# Receiver.net
KiCad netlist of a schematic drawn in Altium Designer
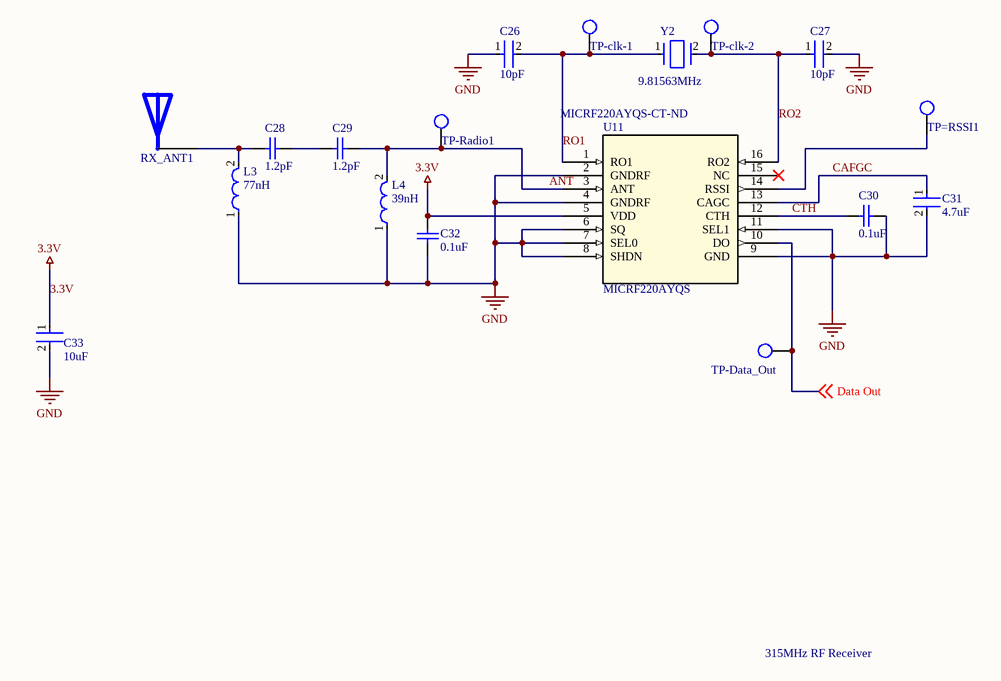
[diagram p0: Receiver.SchDoc]

(export (version "E")
  (design (tool "Eeschema 10.0.6"))
  (components
    (comp (ref "C26")
      (value "10pF")
      (footprint "FP-C0603C-CF-MFG")
      (description "CAP CER 10PF 50V NP0 0603")
      (fields
        (field (name "MANUFACTURER") "KEMET")
        (field (name "MANUFACTURER PART NUMBER") "C0603C100D5GACTU")
      )
      (libsource (lib "Altium Content Vault") (part "b4654b650e69147ec39a6b967a45e02"))
    )
    (comp (ref "C27")
      (value "10pF")
      (footprint "FP-C0603C-CF-MFG")
      (description "CAP CER 10PF 50V NP0 0603")
      (fields
        (field (name "MANUFACTURER") "KEMET")
        (field (name "MANUFACTURER PART NUMBER") "C0603C100D5GACTU")
      )
      (libsource (lib "Altium Content Vault") (part "b4654b650e69147ec39a6b967a45e02"))
    )
    (comp (ref "C28")
      (value "1.2pF")
      (footprint "CAPC1005X55X25LL05T10")
      (fields (field (name "PART NUMBER") "GRM1555C1H1R2WA01D") (field (name "MANUFACTURER") "Murata"))
      (libsource (lib "Altium Content Vault") (part "CAP"))
    )
    (comp (ref "C29")
      (value "1.2pF")
      (footprint "CAPC1005X55X25LL05T10")
      (fields (field (name "PART NUMBER") "GRM1555C1H1R2WA01D") (field (name "MANUFACTURER") "Murata"))
      (libsource (lib "Altium Content Vault") (part "CAP"))
    )
    (comp (ref "C30")
      (value "0.1uF")
      (footprint "CAPC1005X56X25LL10T15")
      (fields
        (field (name "MANUFACTURER") "AVX Interconnect / Elco")
        (field (name "PART NUMBER") "04026D104KAT2A")
      )
      (libsource (lib "Altium Content Vault") (part "CAP"))
    )
    (comp (ref "C31")
      (value "4.7uF")
      (footprint "FP-C1005-050-0_15-IPC_C")
      (description "CAP CER 4.7UF 6.3V X5R 0402")
      (fields (field (name "VOLTAGE") "6.3V") (field (name "TOLERANCE") "20%"))
      (libsource (lib "Altium Content Vault") (part "02cd4be3c70576c341d710602a673aa"))
    )
    (comp (ref "C32")
      (value "0.1uF")
      (footprint "CAPC1005X56X25LL10T15")
      (fields
        (field (name "MANUFACTURER") "AVX Interconnect / Elco")
        (field (name "PART NUMBER") "04026D104KAT2A")
      )
      (libsource (lib "Altium Content Vault") (part "CAP"))
    )
    (comp (ref "C33")
      (value "10uF")
      (footprint "FP-C0805C-DG-MFG")
      (description "CAP CER 10UF 10V X5R 0805")
      (fields (field (name "TOLERANCE") "10%") (field (name "MANUFACTURER PART NUMBER") "C0805C106K8PACTU"))
      (libsource (lib "Altium Content Vault") (part "11868f565c42a9108669ba33697ecf6"))
    )
    (comp (ref "L3")
      (value "77nH")
      (footprint "FP-LQW15CN_10-MFG")
      (description "Wire Wound Ferrite RF Inductor For Automotive 77nH ±5% 1100mA 0.09Ω 0402 (1005)")
      (fields (field (name "TOLERANCE") "5%"))
      (libsource (lib "Altium Content Vault") (part "725321dda6339637d4d059423bc1c3c"))
    )
    (comp (ref "L4")
      (value "39nH")
      (footprint "FP-LQW15AN_80-MFG")
      (description "Wire Wound RF Inductor 39nH ±5% 530mA 0.456Ω 0402 (1005)")
      (fields (field (name "TOLERANCE") "5%"))
      (libsource (lib "Altium Content Vault") (part "725321dda6339637d4d059423bc1c3c"))
    )
    (comp (ref "RX_ANT1")
      (value "RX Antenna")
      (footprint "RX_Antenna")
      (libsource (lib "team6") (part "RX Antenna"))
    )
    (comp (ref "TP-clk-1")
      (value "TP_1206")
      (footprint "TP-SMC-1206")
      (description "Test Point SMD 1206")
      (fields
        (field (name "MANUFACTURER") "TE Connectivity (Tyco Electronics)")
        (field (name "MANUFACTURER PART NUMBER") "1625854-1")
      )
      (libsource (lib "Mechanical") (part "TP_1206"))
    )
    (comp (ref "TP-clk-2")
      (value "TP_1206")
      (footprint "TP-SMC-1206")
      (description "Test Point SMD 1206")
      (fields
        (field (name "MANUFACTURER") "TE Connectivity (Tyco Electronics)")
        (field (name "MANUFACTURER PART NUMBER") "1625854-1")
      )
      (libsource (lib "Mechanical") (part "TP_1206"))
    )
    (comp (ref "TP-Data_Out")
      (value "TP_1206")
      (footprint "TP-SMC-1206")
      (description "Test Point SMD 1206")
      (fields
        (field (name "MANUFACTURER") "TE Connectivity (Tyco Electronics)")
        (field (name "MANUFACTURER PART NUMBER") "1625854-1")
      )
      (libsource (lib "Mechanical") (part "TP_1206"))
    )
    (comp (ref "TP-Radio1")
      (value "TP_1206")
      (footprint "TP-SMC-1206")
      (description "Test Point SMD 1206")
      (fields
        (field (name "MANUFACTURER") "TE Connectivity (Tyco Electronics)")
        (field (name "MANUFACTURER PART NUMBER") "1625854-1")
      )
      (libsource (lib "Mechanical") (part "TP_1206"))
    )
    (comp (ref "TP=RSSI1")
      (value "TP_1206")
      (footprint "TP-SMC-1206")
      (description "Test Point SMD 1206")
      (fields
        (field (name "MANUFACTURER") "TE Connectivity (Tyco Electronics)")
        (field (name "MANUFACTURER PART NUMBER") "1625854-1")
      )
      (libsource (lib "Mechanical") (part "TP_1206"))
    )
    (comp (ref "U11")
      (value "MICRF220AYQS")
      (footprint "SOP63P600X175-16N")
      (description "No Description Available")
      (fields
        (field (name "SUPPLIER PART NUMBER 1") "MICRF220AYQS-CT-ND")
        (field (name "COPYRIGHT") "Copyright (C) 2022 Ultra Librarian. All rights reserved.")
      )
      (libsource (lib "MICRF220AYQS") (part "MICRF220AYQS"))
    )
    (comp (ref "Y2")
      (value "9.81563MHz")
      (footprint "FP-ABM7-MFG")
      (description "Crystal 9.81563MHz ±30ppm 10pF SMD-2 6mm x 3.5mm")
      (libsource (lib "Altium Content Vault") (part "c23a69dc6c9e2f18f2079038eb95dd1"))
    )
  )
  (nets
    (net (code "1") (name "/ANT") (class "Default")
      (node (ref "C29") (pin "2") (pinfunction "2_2") (pintype "passive"))
      (node (ref "L4") (pin "2") (pinfunction "2_2") (pintype "passive"))
      (node (ref "TP-Radio1") (pin "1") (pintype "passive"))
      (node (ref "U11") (pin "3") (pinfunction "ANT_3") (pintype "input"))
    )
    (net (code "2") (name "/CAFGC") (class "Default")
      (node (ref "C31") (pin "1") (pinfunction "1_1") (pintype "passive"))
      (node (ref "U11") (pin "13") (pinfunction "CAGC_13") (pintype "passive"))
    )
    (net (code "3") (name "/CTH") (class "Default")
      (node (ref "C30") (pin "1") (pinfunction "1_1") (pintype "passive"))
      (node (ref "U11") (pin "12") (pinfunction "CTH_12") (pintype "passive"))
    )
    (net (code "4") (name "/RO1") (class "Default")
      (node (ref "C26") (pin "2") (pinfunction "2_2") (pintype "passive"))
      (node (ref "TP-clk-1") (pin "1") (pintype "passive"))
      (node (ref "U11") (pin "1") (pinfunction "RO1_1") (pintype "input"))
      (node (ref "Y2") (pin "1") (pinfunction "1_1") (pintype "passive"))
    )
    (net (code "5") (name "/RO2") (class "Default")
      (node (ref "C27") (pin "1") (pinfunction "1_1") (pintype "passive"))
      (node (ref "TP-clk-2") (pin "1") (pintype "passive"))
      (node (ref "U11") (pin "16") (pinfunction "RO2_16") (pintype "input"))
      (node (ref "Y2") (pin "2") (pinfunction "2_2") (pintype "passive"))
    )
    (net (code "6") (name "3.3V") (class "Default")
      (node (ref "C32") (pin "1") (pinfunction "1_1") (pintype "passive"))
      (node (ref "C33") (pin "1") (pinfunction "1_1") (pintype "passive"))
      (node (ref "U11") (pin "5") (pinfunction "VDD_5") (pintype "power_in"))
    )
    (net (code "7") (name "Data Out") (class "Default")
      (node (ref "TP-Data_Out") (pin "1") (pintype "passive"))
      (node (ref "U11") (pin "10") (pinfunction "DO_10") (pintype "output"))
    )
    (net (code "8") (name "GND") (class "Default")
      (node (ref "C26") (pin "1") (pinfunction "1_1") (pintype "passive"))
      (node (ref "C27") (pin "2") (pinfunction "2_2") (pintype "passive"))
      (node (ref "C30") (pin "2") (pinfunction "2_2") (pintype "passive"))
      (node (ref "C31") (pin "2") (pinfunction "2_2") (pintype "passive"))
      (node (ref "C32") (pin "2") (pinfunction "2_2") (pintype "passive"))
      (node (ref "C33") (pin "2") (pinfunction "2_2") (pintype "passive"))
      (node (ref "L3") (pin "1") (pinfunction "1_1") (pintype "passive"))
      (node (ref "L4") (pin "1") (pinfunction "1_1") (pintype "passive"))
      (node (ref "U11") (pin "11") (pinfunction "SEL1_11") (pintype "input"))
      (node (ref "U11") (pin "2") (pinfunction "GNDRF_2") (pintype "power_in"))
      (node (ref "U11") (pin "4") (pinfunction "GNDRF_4") (pintype "power_in"))
      (node (ref "U11") (pin "6") (pinfunction "SQ_6") (pintype "input"))
      (node (ref "U11") (pin "7") (pinfunction "SEL0_7") (pintype "input"))
      (node (ref "U11") (pin "8") (pinfunction "SHDN_8") (pintype "input"))
      (node (ref "U11") (pin "9") (pinfunction "GND_9") (pintype "power_in"))
    )
    (net (code "9") (name "Net-(C28-Pad1)") (class "Default")
      (node (ref "C28") (pin "1") (pinfunction "1_1") (pintype "passive"))
      (node (ref "L3") (pin "2") (pinfunction "2_2") (pintype "passive"))
      (node (ref "RX_ANT1") (pin "0") (pinfunction "0_0") (pintype "passive"))
    )
    (net (code "10") (name "Net-(C28-Pad2)") (class "Default")
      (node (ref "C28") (pin "2") (pinfunction "2_2") (pintype "passive"))
      (node (ref "C29") (pin "1") (pinfunction "1_1") (pintype "passive"))
    )
    (net (code "11") (name "Net-(U11-RSSI)") (class "Default")
      (node (ref "TP=RSSI1") (pin "1") (pintype "passive"))
      (node (ref "U11") (pin "14") (pinfunction "RSSI_14") (pintype "output"))
    )
    (net (code "12") (name "unconnected-(U11-NC-Pad15)") (class "Default")
      (node (ref "U11") (pin "15") (pinfunction "NC_15") (pintype "passive+no_connect"))
    )
  )
)
